# System.net
KiCad netlist of a schematic drawn in Altium Designer
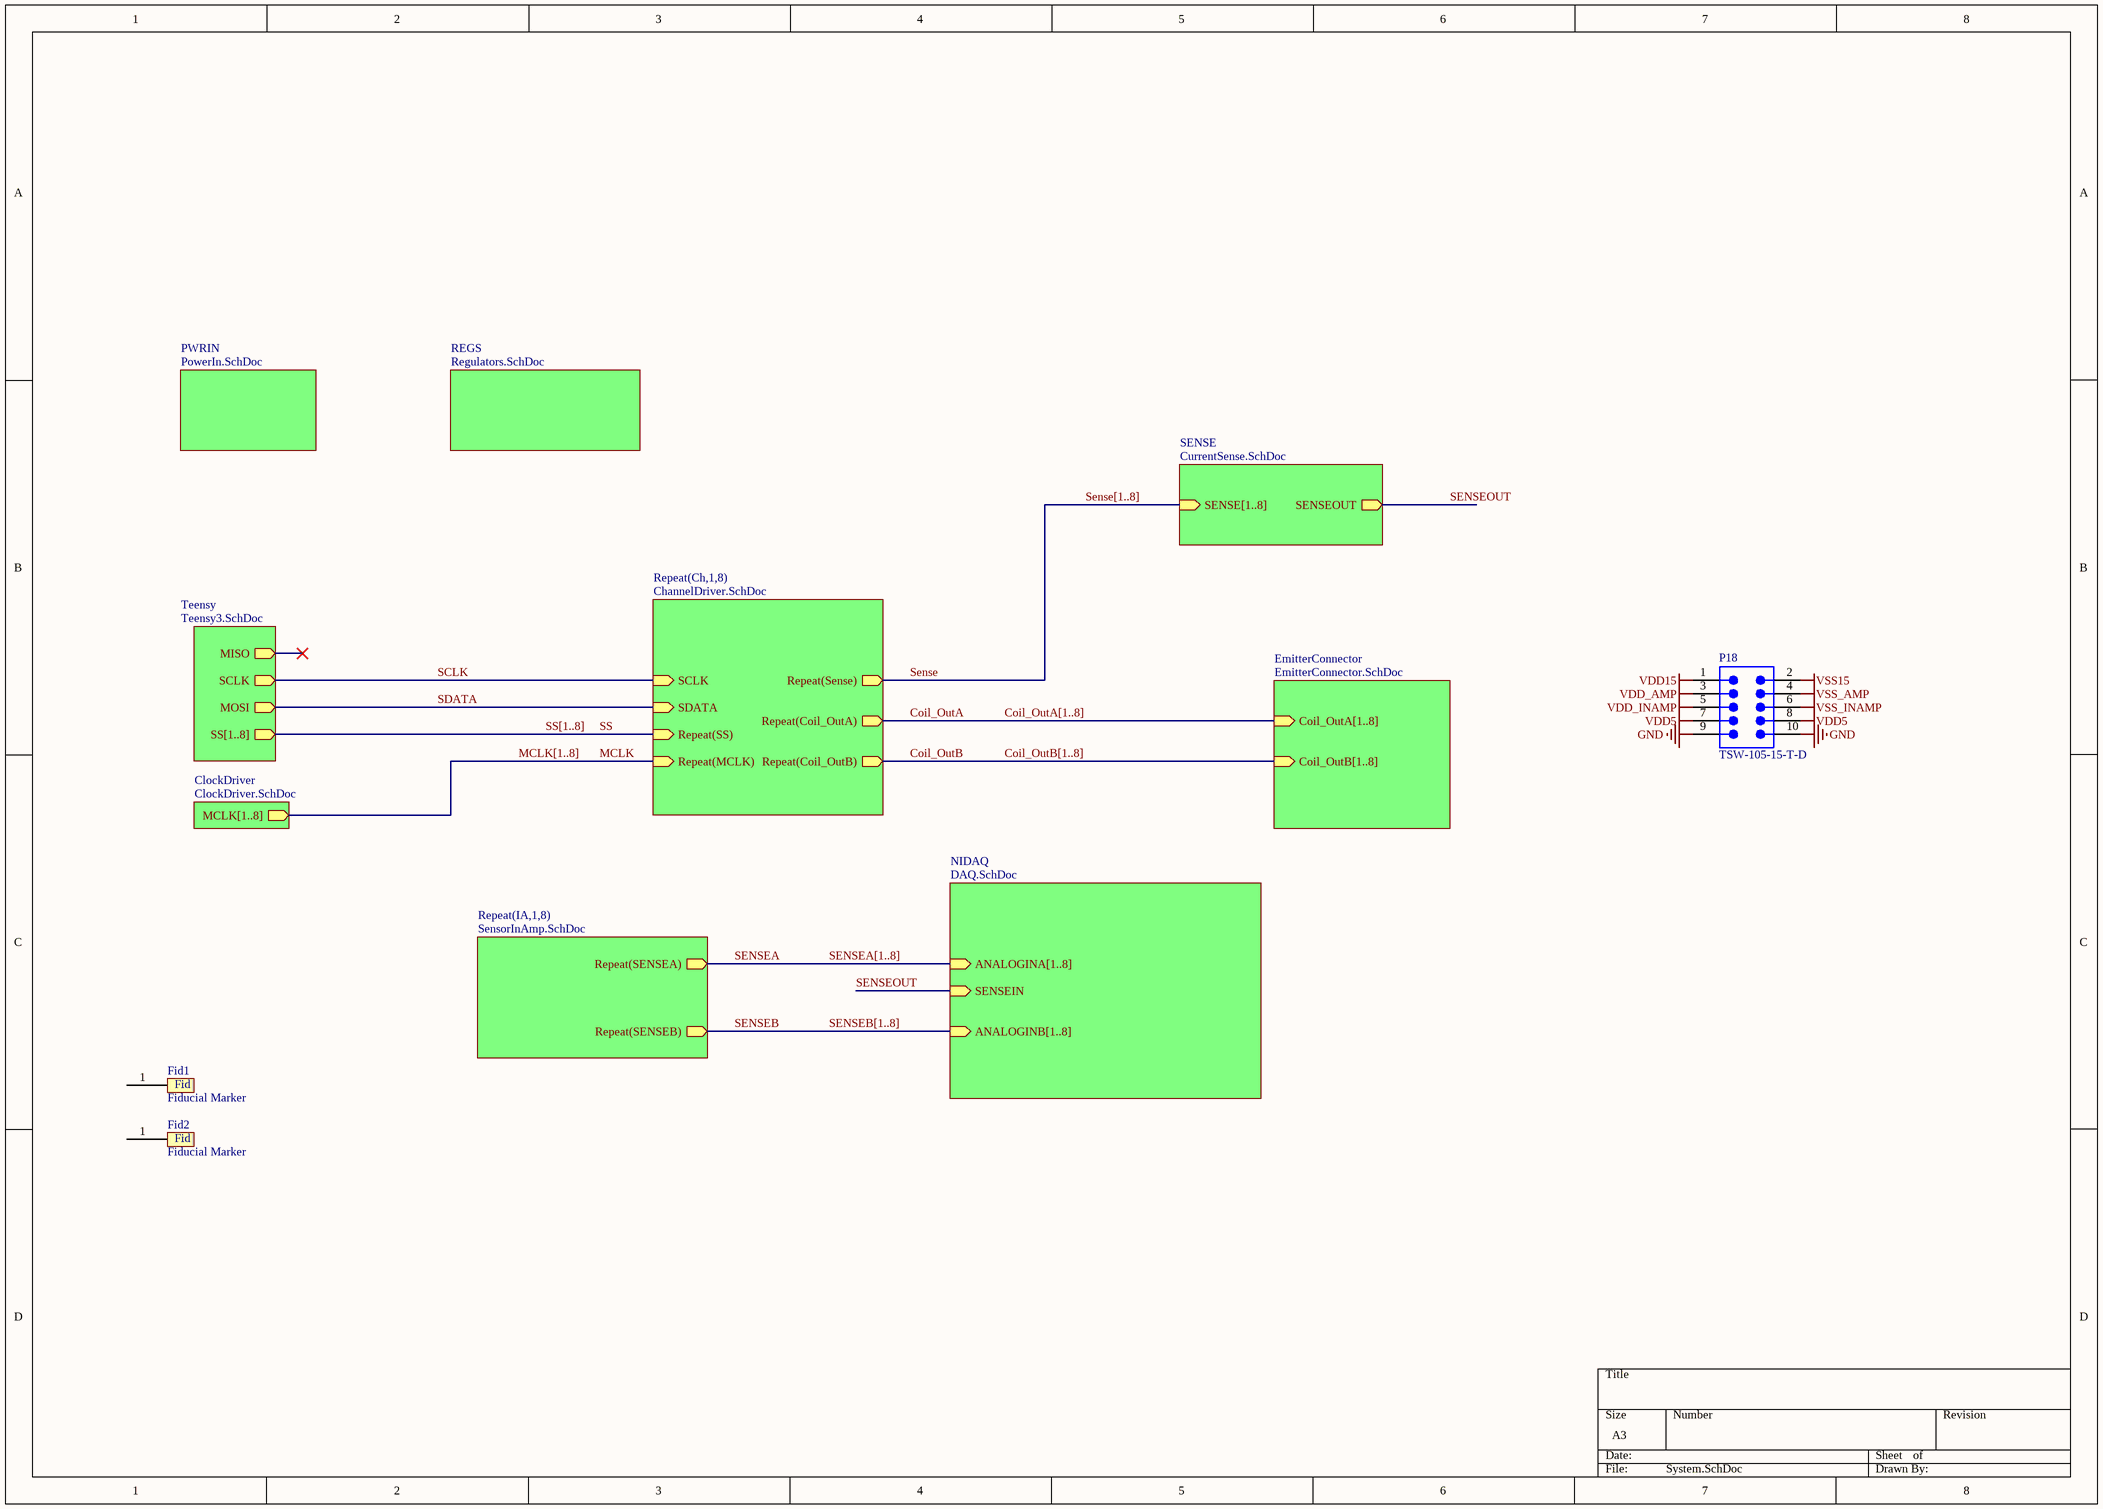
[diagram p0: System.SchDoc]

(export (version "E")
  (design (tool "Eeschema 10.0.6"))
  (components
    (comp (ref "Fid1")
      (value "Fiducial Marker")
      (footprint "Fiducial")
      (libsource (lib "AnserEMT") (part "Fiducial Marker"))
    )
    (comp (ref "Fid2")
      (value "Fiducial Marker")
      (footprint "Fiducial")
      (libsource (lib "AnserEMT") (part "Fiducial Marker"))
    )
    (comp (ref "P18")
      (value "TSW-105-15-T-D")
      (footprint "SMTC-TSW-105-15-X-D")
      (fields (field (name "MANUFACTURER") "Samtec"))
      (libsource (lib "Altium Content Vault") (part "CMP-1024-00368-1"))
    )
  )
  (nets
    (net (code "75") (name "GND") (class "Default")
      (node (ref "P18") (pin "10") (pinfunction "10_10") (pintype "passive"))
      (node (ref "P18") (pin "9") (pinfunction "9_9") (pintype "passive"))
    )
    (net (code "76") (name "VDD5") (class "Default")
      (node (ref "P18") (pin "7") (pinfunction "7_7") (pintype "passive"))
      (node (ref "P18") (pin "8") (pinfunction "8_8") (pintype "passive"))
    )
    (net (code "77") (name "VDD15") (class "Default")
      (node (ref "P18") (pin "1") (pinfunction "1_1") (pintype "passive"))
    )
    (net (code "78") (name "VDD_AMP") (class "Default")
      (node (ref "P18") (pin "3") (pinfunction "3_3") (pintype "passive"))
    )
    (net (code "79") (name "VDD_INAMP") (class "Default")
      (node (ref "P18") (pin "5") (pinfunction "5_5") (pintype "passive"))
    )
    (net (code "80") (name "VSS15") (class "Default")
      (node (ref "P18") (pin "2") (pinfunction "2_2") (pintype "passive"))
    )
    (net (code "81") (name "VSS_AMP") (class "Default")
      (node (ref "P18") (pin "4") (pinfunction "4_4") (pintype "passive"))
    )
    (net (code "82") (name "VSS_INAMP") (class "Default")
      (node (ref "P18") (pin "6") (pinfunction "6_6") (pintype "passive"))
    )
    (net (code "83") (name "unconnected-(Fid1-Pad1)") (class "Default")
      (node (ref "Fid1") (pin "1") (pintype "passive"))
    )
    (net (code "84") (name "unconnected-(Fid2-Pad1)") (class "Default")
      (node (ref "Fid2") (pin "1") (pintype "passive"))
    )
  )
)
